# SGP30_Rev_D.net
KiCad netlist of a schematic drawn in EAGLE
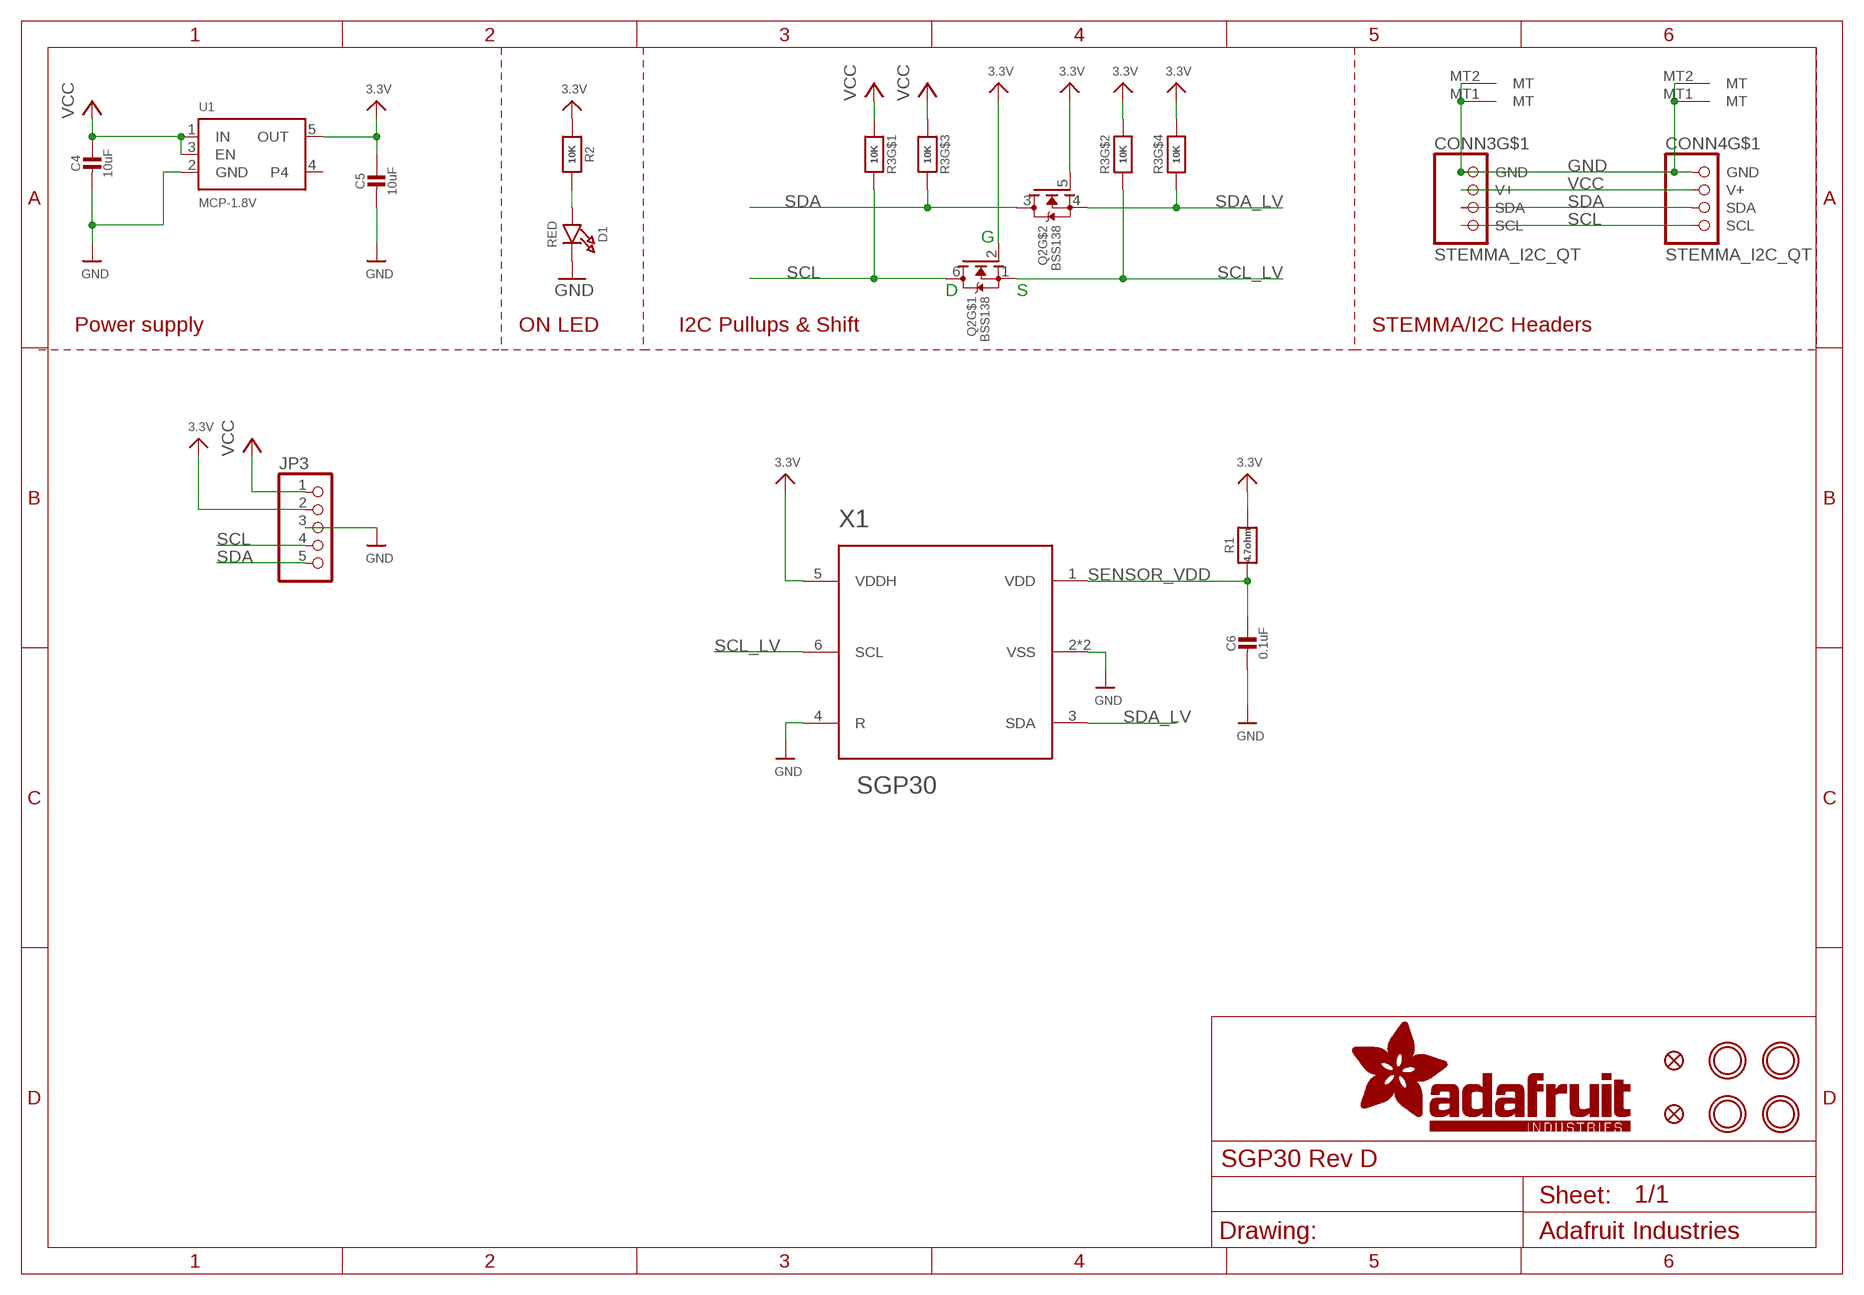
[diagram p0: schematic, sheet 1]

(export (version "E")
  (design (tool "Eeschema 10.0.6"))
  (components
    (comp (ref "C4")
      (value "10uF")
      (footprint "eagle-import:0805-NO")
      (libsource (lib "eagle-import") (part "CAP_CERAMIC0805-NOOUTLINE"))
    )
    (comp (ref "C5")
      (value "10uF")
      (footprint "eagle-import:0805-NO")
      (libsource (lib "eagle-import") (part "CAP_CERAMIC0805-NOOUTLINE"))
    )
    (comp (ref "C6")
      (value "0.1uF")
      (footprint "eagle-import:0603-NO")
      (libsource (lib "eagle-import") (part "CAP_CERAMIC0603_NO"))
    )
    (comp (ref "CONN3")
      (value "STEMMA_I2C_QT")
      (footprint "eagle-import:JST_SH4")
      (libsource (lib "eagle-import") (part "STEMMA_I2C_QT"))
    )
    (comp (ref "CONN4")
      (value "STEMMA_I2C_QT")
      (footprint "eagle-import:JST_SH4")
      (libsource (lib "eagle-import") (part "STEMMA_I2C_QT"))
    )
    (comp (ref "D1")
      (value "RED")
      (footprint "eagle-import:CHIPLED_0603_NOOUTLINE")
      (libsource (lib "eagle-import") (part "LED0603_NOOUTLINE"))
    )
    (comp (ref "FID3")
      (value "FIDUCIAL_1MM")
      (footprint "eagle-import:FIDUCIAL_1MM")
      (libsource (lib "eagle-import") (part "FIDUCIAL_1MM"))
    )
    (comp (ref "FID4")
      (value "FIDUCIAL_1MM")
      (footprint "eagle-import:FIDUCIAL_1MM")
      (libsource (lib "eagle-import") (part "FIDUCIAL_1MM"))
    )
    (comp (ref "JP3")
      (value "HEADER-1X570MIL")
      (footprint "eagle-import:1X05_ROUND_70")
      (libsource (lib "eagle-import") (part "HEADER-1X570MIL"))
    )
    (comp (ref "Q2")
      (value "BSS138")
      (footprint "eagle-import:SOT363")
      (libsource (lib "eagle-import") (part "MOSFET-N_DUAL"))
    )
    (comp (ref "R1")
      (value "4.7ohm")
      (footprint "eagle-import:0603-NO")
      (libsource (lib "eagle-import") (part "RESISTOR_0603_NOOUT"))
    )
    (comp (ref "R2")
      (value "10K")
      (footprint "eagle-import:0603-NO")
      (libsource (lib "eagle-import") (part "RESISTOR_0603_NOOUT"))
    )
    (comp (ref "R3")
      (value "10K")
      (footprint "eagle-import:RESPACK_4X0603")
      (libsource (lib "eagle-import") (part "RESISTOR_4PACK"))
    )
    (comp (ref "U$28")
      (value "MOUNTINGHOLE2.5")
      (footprint "eagle-import:MOUNTINGHOLE_2.5_PLATED")
      (libsource (lib "eagle-import") (part "MOUNTINGHOLE2.5"))
    )
    (comp (ref "U$29")
      (value "MOUNTINGHOLE2.5")
      (footprint "eagle-import:MOUNTINGHOLE_2.5_PLATED")
      (libsource (lib "eagle-import") (part "MOUNTINGHOLE2.5"))
    )
    (comp (ref "U$31")
      (value "MOUNTINGHOLE2.5")
      (footprint "eagle-import:MOUNTINGHOLE_2.5_PLATED")
      (libsource (lib "eagle-import") (part "MOUNTINGHOLE2.5"))
    )
    (comp (ref "U$32")
      (value "MOUNTINGHOLE2.5")
      (footprint "eagle-import:MOUNTINGHOLE_2.5_PLATED")
      (libsource (lib "eagle-import") (part "MOUNTINGHOLE2.5"))
    )
    (comp (ref "U1")
      (value "MCP-1.8V")
      (footprint "eagle-import:SOT23-5")
      (libsource (lib "eagle-import") (part "VREG_SOT23-5"))
    )
    (comp (ref "X1")
      (value "SGP30")
      (footprint "eagle-import:SGP30")
      (libsource (lib "eagle-import") (part "SGP30"))
    )
  )
  (nets
    (net (code "1") (name "/SCL") (class "Default")
      (node (ref "CONN3") (pin "4") (pinfunction "SCL_4") (pintype "passive"))
      (node (ref "CONN4") (pin "4") (pinfunction "SCL_4") (pintype "passive"))
      (node (ref "JP3") (pin "4") (pinfunction "4_4") (pintype "passive"))
      (node (ref "Q2") (pin "6") (pinfunction "D_6") (pintype "bidirectional"))
      (node (ref "R3") (pin "8") (pinfunction "2_8") (pintype "passive"))
    )
    (net (code "2") (name "/SCL_LV") (class "Default")
      (node (ref "Q2") (pin "1") (pinfunction "S_1") (pintype "bidirectional"))
      (node (ref "R3") (pin "7") (pinfunction "2_7") (pintype "passive"))
      (node (ref "X1") (pin "6") (pinfunction "SCL_6") (pintype "bidirectional"))
    )
    (net (code "3") (name "/SDA") (class "Default")
      (node (ref "CONN3") (pin "3") (pinfunction "SDA_3") (pintype "passive"))
      (node (ref "CONN4") (pin "3") (pinfunction "SDA_3") (pintype "passive"))
      (node (ref "JP3") (pin "5") (pinfunction "5_5") (pintype "passive"))
      (node (ref "Q2") (pin "3") (pinfunction "D_3") (pintype "bidirectional"))
      (node (ref "R3") (pin "6") (pinfunction "2_6") (pintype "passive"))
    )
    (net (code "4") (name "/SDA_LV") (class "Default")
      (node (ref "Q2") (pin "4") (pinfunction "S_4") (pintype "bidirectional"))
      (node (ref "R3") (pin "5") (pinfunction "2_5") (pintype "passive"))
      (node (ref "X1") (pin "3") (pinfunction "SDA_3") (pintype "bidirectional"))
    )
    (net (code "5") (name "/SENSOR_VDD") (class "Default")
      (node (ref "C6") (pin "1") (pinfunction "1_1") (pintype "passive"))
      (node (ref "R1") (pin "1") (pinfunction "1_1") (pintype "passive"))
      (node (ref "X1") (pin "1") (pinfunction "VDD_1") (pintype "bidirectional"))
    )
    (net (code "6") (name "3.3V") (class "Default")
      (node (ref "C5") (pin "1") (pinfunction "1_1") (pintype "passive"))
      (node (ref "JP3") (pin "2") (pinfunction "2_2") (pintype "passive"))
      (node (ref "Q2") (pin "2") (pinfunction "G_2") (pintype "bidirectional"))
      (node (ref "Q2") (pin "5") (pinfunction "G_5") (pintype "bidirectional"))
      (node (ref "R1") (pin "2") (pinfunction "2_2") (pintype "passive"))
      (node (ref "R2") (pin "1") (pinfunction "1_1") (pintype "passive"))
      (node (ref "R3") (pin "2") (pinfunction "1_2") (pintype "passive"))
      (node (ref "R3") (pin "4") (pinfunction "1_4") (pintype "passive"))
      (node (ref "U1") (pin "5") (pinfunction "OUT_5") (pintype "power_in"))
      (node (ref "X1") (pin "5") (pinfunction "VDDH_5") (pintype "bidirectional"))
    )
    (net (code "7") (name "GND") (class "Default")
      (node (ref "C4") (pin "2") (pinfunction "2_2") (pintype "passive"))
      (node (ref "C5") (pin "2") (pinfunction "2_2") (pintype "passive"))
      (node (ref "C6") (pin "2") (pinfunction "2_2") (pintype "passive"))
      (node (ref "CONN3") (pin "1") (pinfunction "GND_1") (pintype "passive"))
      (node (ref "CONN3") (pin "MT1") (pinfunction "MT_MT1") (pintype "bidirectional"))
      (node (ref "CONN3") (pin "MT2") (pinfunction "MT_MT2") (pintype "bidirectional"))
      (node (ref "CONN4") (pin "1") (pinfunction "GND_1") (pintype "passive"))
      (node (ref "CONN4") (pin "MT1") (pinfunction "MT_MT1") (pintype "bidirectional"))
      (node (ref "CONN4") (pin "MT2") (pinfunction "MT_MT2") (pintype "bidirectional"))
      (node (ref "D1") (pin "C") (pinfunction "C_C") (pintype "passive"))
      (node (ref "JP3") (pin "3") (pinfunction "3_3") (pintype "passive"))
      (node (ref "U1") (pin "2") (pinfunction "GND_2") (pintype "power_in"))
      (node (ref "X1") (pin "2") (pinfunction "VSS_2") (pintype "bidirectional"))
      (node (ref "X1") (pin "4") (pinfunction "R_4") (pintype "bidirectional"))
      (node (ref "X1") (pin "P$7") (pinfunction "VSS_P$7") (pintype "bidirectional"))
    )
    (net (code "8") (name "Net-(D1-PadA)") (class "Default")
      (node (ref "D1") (pin "A") (pinfunction "A_A") (pintype "passive"))
      (node (ref "R2") (pin "2") (pinfunction "2_2") (pintype "passive"))
    )
    (net (code "9") (name "VCC") (class "Default")
      (node (ref "C4") (pin "1") (pinfunction "1_1") (pintype "passive"))
      (node (ref "CONN3") (pin "2") (pinfunction "V+_2") (pintype "passive"))
      (node (ref "CONN4") (pin "2") (pinfunction "V+_2") (pintype "passive"))
      (node (ref "JP3") (pin "1") (pinfunction "1_1") (pintype "passive"))
      (node (ref "R3") (pin "1") (pinfunction "1_1") (pintype "passive"))
      (node (ref "R3") (pin "3") (pinfunction "1_3") (pintype "passive"))
      (node (ref "U1") (pin "1") (pinfunction "IN_1") (pintype "power_in"))
      (node (ref "U1") (pin "3") (pinfunction "EN_3") (pintype "input"))
    )
    (net (code "10") (name "unconnected-(U1-P4-Pad4)") (class "Default")
      (node (ref "U1") (pin "4") (pinfunction "P4_4") (pintype "bidirectional"))
    )
  )
)
